# Dual_7seg_Rev0.net
KiCad netlist of a schematic drawn in EAGLE
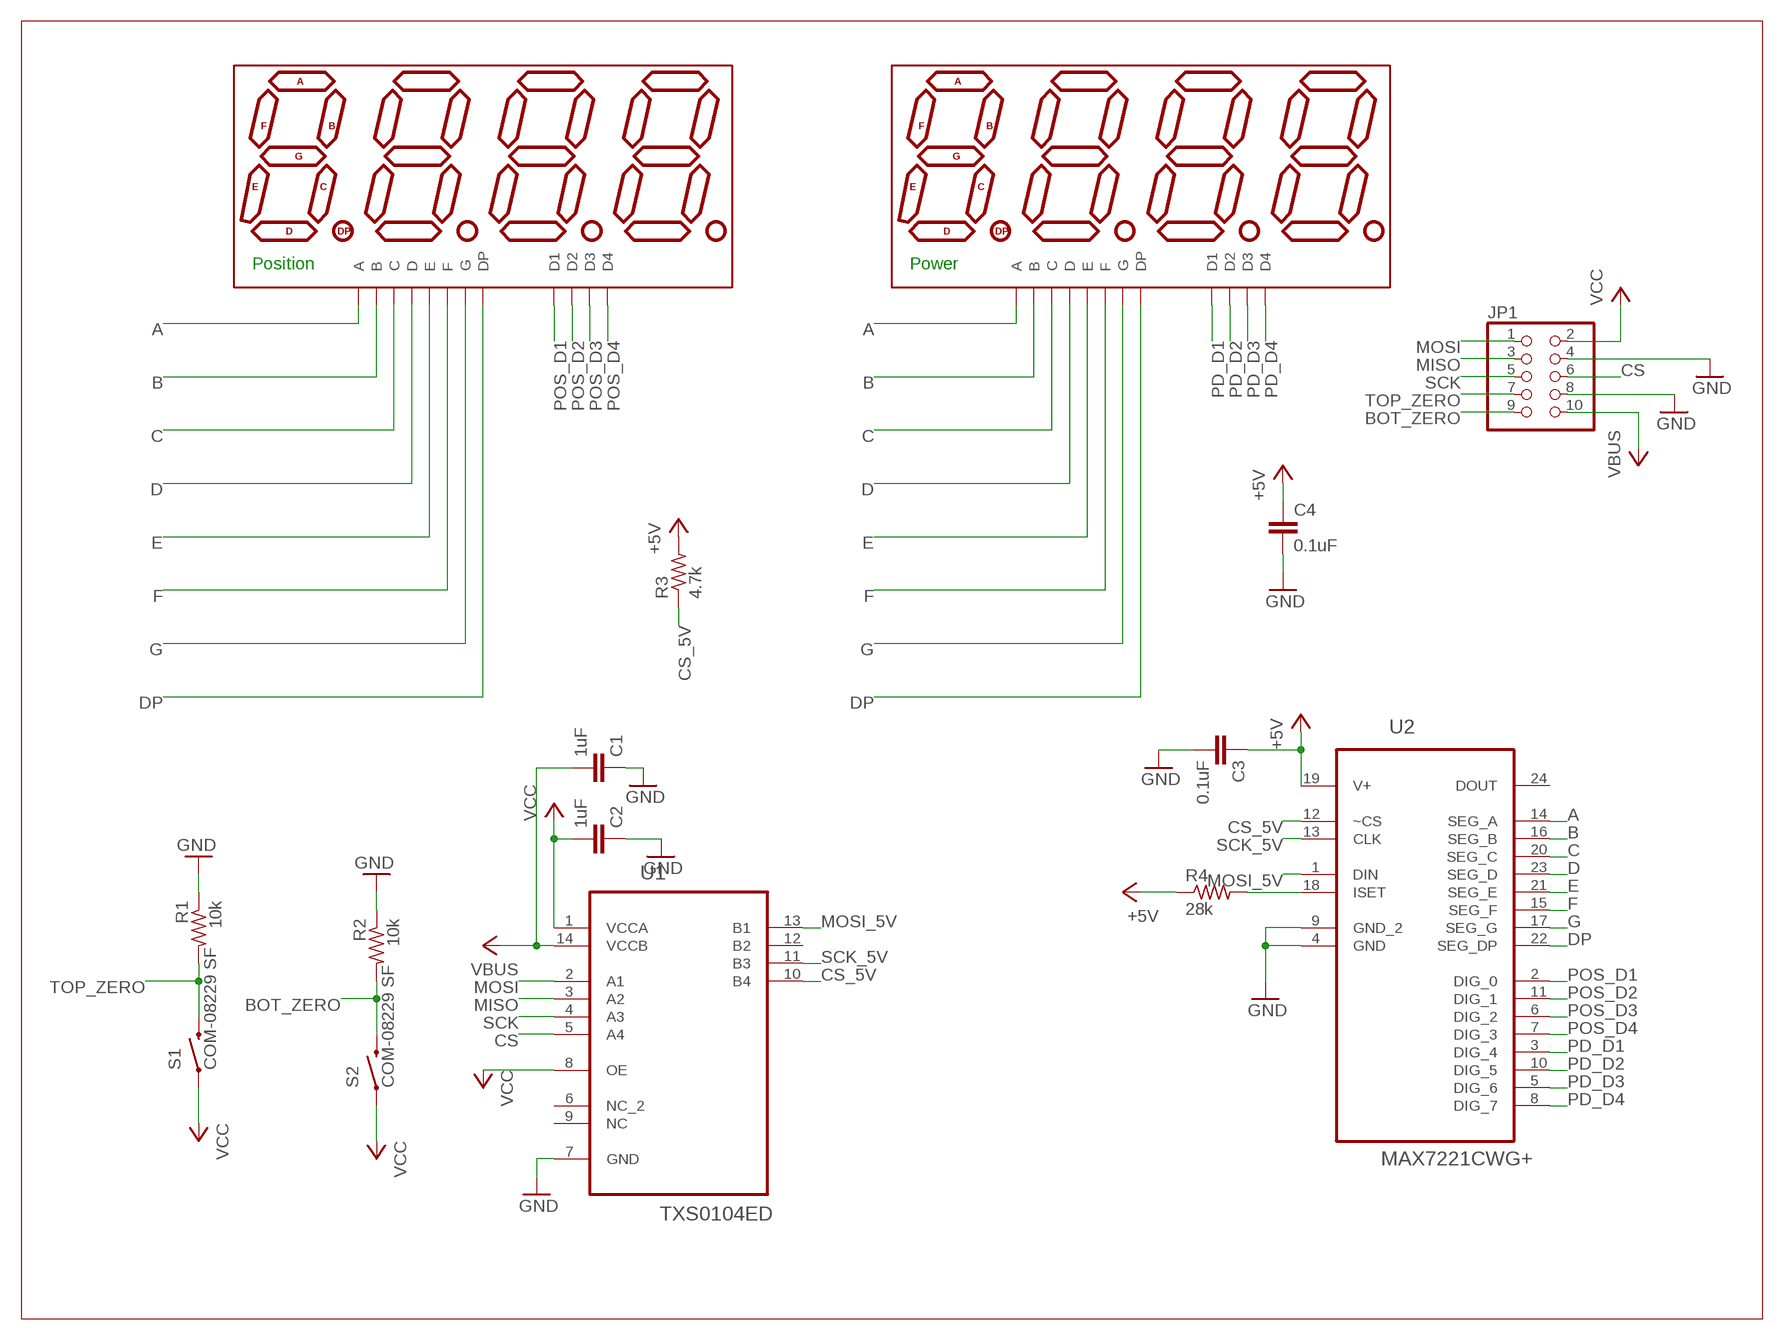
[diagram p0: schematic, sheet 1]

(export (version "E")
  (design (tool "Eeschema 10.0.6"))
  (components
    (comp (ref "C1")
      (value "1uF")
      (footprint "eagle-import:C0402")
      (libsource (lib "eagle-import") (part "C-EUC0402"))
    )
    (comp (ref "C2")
      (value "1uF")
      (footprint "eagle-import:C0402")
      (libsource (lib "eagle-import") (part "C-EUC0402"))
    )
    (comp (ref "C3")
      (value "0.1uF")
      (footprint "eagle-import:C0402")
      (libsource (lib "eagle-import") (part "C-EUC0402"))
    )
    (comp (ref "C4")
      (value "0.1uF")
      (footprint "eagle-import:C0402")
      (libsource (lib "eagle-import") (part "C-EUC0402"))
    )
    (comp (ref "DISP1")
      (value "ATA8041AW")
      (footprint "eagle-import:7-SEGMENT-4DIGIT-20MM")
      (libsource (lib "eagle-import") (part "7-SEGMENT-4DIGIT-20MM-WHITE"))
    )
    (comp (ref "DISP2")
      (value "ATA8041AW")
      (footprint "eagle-import:7-SEGMENT-4DIGIT-20MM")
      (libsource (lib "eagle-import") (part "7-SEGMENT-4DIGIT-20MM-WHITE"))
    )
    (comp (ref "JP1")
      (value "PINHD-2X5")
      (footprint "eagle-import:2X05")
      (libsource (lib "eagle-import") (part "PINHD-2X5"))
    )
    (comp (ref "R1")
      (value "10k")
      (footprint "eagle-import:R0402")
      (libsource (lib "eagle-import") (part "R-US_R0402"))
    )
    (comp (ref "R2")
      (value "10k")
      (footprint "eagle-import:R0402")
      (libsource (lib "eagle-import") (part "R-US_R0402"))
    )
    (comp (ref "R3")
      (value "4.7k")
      (footprint "eagle-import:R0402")
      (libsource (lib "eagle-import") (part "R-US_R0402"))
    )
    (comp (ref "R4")
      (value "28k")
      (footprint "eagle-import:R0402")
      (libsource (lib "eagle-import") (part "R-US_R0402"))
    )
    (comp (ref "S1")
      (value "COM-08229 SF")
      (footprint "eagle-import:TACTILE-SWITCH-1101NE")
      (libsource (lib "eagle-import") (part "SWITCH-MOMENTARY-2SMD-1101NE"))
    )
    (comp (ref "S2")
      (value "COM-08229 SF")
      (footprint "eagle-import:TACTILE-SWITCH-1101NE")
      (libsource (lib "eagle-import") (part "SWITCH-MOMENTARY-2SMD-1101NE"))
    )
    (comp (ref "U1")
      (value "TXS0104ED")
      (footprint "eagle-import:SOIC127P600X175-14N")
      (libsource (lib "eagle-import") (part "TXS0104ED"))
    )
    (comp (ref "U2")
      (value "MAX7221CWG+")
      (footprint "eagle-import:SOIC127P1032X265-24N")
      (libsource (lib "eagle-import") (part "MAX7221CWG+"))
    )
  )
  (nets
    (net (code "1") (name "+5V") (class "Default")
      (node (ref "C1") (pin "2") (pinfunction "2_2") (pintype "passive"))
      (node (ref "C3") (pin "1") (pinfunction "1_1") (pintype "passive"))
      (node (ref "C4") (pin "1") (pinfunction "1_1") (pintype "passive"))
      (node (ref "JP1") (pin "10") (pinfunction "10_10") (pintype "passive"))
      (node (ref "R3") (pin "2") (pinfunction "2_2") (pintype "passive"))
      (node (ref "R4") (pin "1") (pinfunction "1_1") (pintype "passive"))
      (node (ref "U1") (pin "14") (pinfunction "VCCB_14") (pintype "power_in"))
      (node (ref "U2") (pin "19") (pinfunction "V+_19") (pintype "power_in"))
    )
    (net (code "2") (name "/A") (class "Default")
      (node (ref "DISP1") (pin "11") (pinfunction "A_11") (pintype "bidirectional"))
      (node (ref "DISP2") (pin "11") (pinfunction "A_11") (pintype "bidirectional"))
      (node (ref "U2") (pin "14") (pinfunction "SEG_A_14") (pintype "output"))
    )
    (net (code "3") (name "/B") (class "Default")
      (node (ref "DISP1") (pin "7") (pinfunction "B_7") (pintype "bidirectional"))
      (node (ref "DISP2") (pin "7") (pinfunction "B_7") (pintype "bidirectional"))
      (node (ref "U2") (pin "16") (pinfunction "SEG_B_16") (pintype "output"))
    )
    (net (code "4") (name "/BOT_ZERO") (class "Default")
      (node (ref "JP1") (pin "9") (pinfunction "9_9") (pintype "passive"))
      (node (ref "R2") (pin "2") (pinfunction "2_2") (pintype "passive"))
      (node (ref "S2") (pin "2") (pinfunction "2_2") (pintype "passive"))
    )
    (net (code "5") (name "/C") (class "Default")
      (node (ref "DISP1") (pin "4") (pinfunction "C_4") (pintype "bidirectional"))
      (node (ref "DISP2") (pin "4") (pinfunction "C_4") (pintype "bidirectional"))
      (node (ref "U2") (pin "20") (pinfunction "SEG_C_20") (pintype "output"))
    )
    (net (code "6") (name "/CS") (class "Default")
      (node (ref "JP1") (pin "6") (pinfunction "6_6") (pintype "passive"))
      (node (ref "U1") (pin "5") (pinfunction "A4_5") (pintype "input"))
    )
    (net (code "7") (name "/CS_5V") (class "Default")
      (node (ref "R3") (pin "1") (pinfunction "1_1") (pintype "passive"))
      (node (ref "U1") (pin "10") (pinfunction "B4_10") (pintype "output"))
      (node (ref "U2") (pin "12") (pinfunction "~{CS}_12") (pintype "input"))
    )
    (net (code "8") (name "/D") (class "Default")
      (node (ref "DISP1") (pin "2") (pinfunction "D_2") (pintype "bidirectional"))
      (node (ref "DISP2") (pin "2") (pinfunction "D_2") (pintype "bidirectional"))
      (node (ref "U2") (pin "23") (pinfunction "SEG_D_23") (pintype "output"))
    )
    (net (code "9") (name "/DP") (class "Default")
      (node (ref "DISP1") (pin "3") (pinfunction "DP_3") (pintype "bidirectional"))
      (node (ref "DISP2") (pin "3") (pinfunction "DP_3") (pintype "bidirectional"))
      (node (ref "U2") (pin "22") (pinfunction "SEG_DP_22") (pintype "output"))
    )
    (net (code "10") (name "/E") (class "Default")
      (node (ref "DISP1") (pin "1") (pinfunction "E_1") (pintype "bidirectional"))
      (node (ref "DISP2") (pin "1") (pinfunction "E_1") (pintype "bidirectional"))
      (node (ref "U2") (pin "21") (pinfunction "SEG_E_21") (pintype "output"))
    )
    (net (code "11") (name "/F") (class "Default")
      (node (ref "DISP1") (pin "10") (pinfunction "F_10") (pintype "bidirectional"))
      (node (ref "DISP2") (pin "10") (pinfunction "F_10") (pintype "bidirectional"))
      (node (ref "U2") (pin "15") (pinfunction "SEG_F_15") (pintype "output"))
    )
    (net (code "12") (name "/G") (class "Default")
      (node (ref "DISP1") (pin "5") (pinfunction "G_5") (pintype "bidirectional"))
      (node (ref "DISP2") (pin "5") (pinfunction "G_5") (pintype "bidirectional"))
      (node (ref "U2") (pin "17") (pinfunction "SEG_G_17") (pintype "output"))
    )
    (net (code "13") (name "/MISO") (class "Default")
      (node (ref "JP1") (pin "3") (pinfunction "3_3") (pintype "passive"))
      (node (ref "U1") (pin "3") (pinfunction "A2_3") (pintype "input"))
    )
    (net (code "14") (name "/MOSI") (class "Default")
      (node (ref "JP1") (pin "1") (pinfunction "1_1") (pintype "passive"))
      (node (ref "U1") (pin "2") (pinfunction "A1_2") (pintype "input"))
    )
    (net (code "15") (name "/MOSI_5V") (class "Default")
      (node (ref "U1") (pin "13") (pinfunction "B1_13") (pintype "output"))
      (node (ref "U2") (pin "1") (pinfunction "DIN_1") (pintype "input"))
    )
    (net (code "16") (name "/PD_D1") (class "Default")
      (node (ref "DISP2") (pin "12") (pinfunction "D1_12") (pintype "bidirectional"))
      (node (ref "U2") (pin "3") (pinfunction "DIG_4_3") (pintype "output"))
    )
    (net (code "17") (name "/PD_D2") (class "Default")
      (node (ref "DISP2") (pin "9") (pinfunction "D2_9") (pintype "bidirectional"))
      (node (ref "U2") (pin "10") (pinfunction "DIG_5_10") (pintype "output"))
    )
    (net (code "18") (name "/PD_D3") (class "Default")
      (node (ref "DISP2") (pin "8") (pinfunction "D3_8") (pintype "bidirectional"))
      (node (ref "U2") (pin "5") (pinfunction "DIG_6_5") (pintype "output"))
    )
    (net (code "19") (name "/PD_D4") (class "Default")
      (node (ref "DISP2") (pin "6") (pinfunction "D4_6") (pintype "bidirectional"))
      (node (ref "U2") (pin "8") (pinfunction "DIG_7_8") (pintype "output"))
    )
    (net (code "20") (name "/POS_D1") (class "Default")
      (node (ref "DISP1") (pin "12") (pinfunction "D1_12") (pintype "bidirectional"))
      (node (ref "U2") (pin "2") (pinfunction "DIG_0_2") (pintype "output"))
    )
    (net (code "21") (name "/POS_D2") (class "Default")
      (node (ref "DISP1") (pin "9") (pinfunction "D2_9") (pintype "bidirectional"))
      (node (ref "U2") (pin "11") (pinfunction "DIG_1_11") (pintype "output"))
    )
    (net (code "22") (name "/POS_D3") (class "Default")
      (node (ref "DISP1") (pin "8") (pinfunction "D3_8") (pintype "bidirectional"))
      (node (ref "U2") (pin "6") (pinfunction "DIG_2_6") (pintype "output"))
    )
    (net (code "23") (name "/POS_D4") (class "Default")
      (node (ref "DISP1") (pin "6") (pinfunction "D4_6") (pintype "bidirectional"))
      (node (ref "U2") (pin "7") (pinfunction "DIG_3_7") (pintype "output"))
    )
    (net (code "24") (name "/SCK") (class "Default")
      (node (ref "JP1") (pin "5") (pinfunction "5_5") (pintype "passive"))
      (node (ref "U1") (pin "4") (pinfunction "A3_4") (pintype "input"))
    )
    (net (code "25") (name "/SCK_5V") (class "Default")
      (node (ref "U1") (pin "11") (pinfunction "B3_11") (pintype "output"))
      (node (ref "U2") (pin "13") (pinfunction "CLK_13") (pintype "input"))
    )
    (net (code "26") (name "/TOP_ZERO") (class "Default")
      (node (ref "JP1") (pin "7") (pinfunction "7_7") (pintype "passive"))
      (node (ref "R1") (pin "2") (pinfunction "2_2") (pintype "passive"))
      (node (ref "S1") (pin "2") (pinfunction "2_2") (pintype "passive"))
    )
    (net (code "27") (name "GND") (class "Default")
      (node (ref "C1") (pin "1") (pinfunction "1_1") (pintype "passive"))
      (node (ref "C2") (pin "1") (pinfunction "1_1") (pintype "passive"))
      (node (ref "C3") (pin "2") (pinfunction "2_2") (pintype "passive"))
      (node (ref "C4") (pin "2") (pinfunction "2_2") (pintype "passive"))
      (node (ref "JP1") (pin "4") (pinfunction "4_4") (pintype "passive"))
      (node (ref "JP1") (pin "8") (pinfunction "8_8") (pintype "passive"))
      (node (ref "R1") (pin "1") (pinfunction "1_1") (pintype "passive"))
      (node (ref "R2") (pin "1") (pinfunction "1_1") (pintype "passive"))
      (node (ref "U1") (pin "7") (pinfunction "GND_7") (pintype "passive"))
      (node (ref "U2") (pin "4") (pinfunction "GND_4") (pintype "passive"))
      (node (ref "U2") (pin "9") (pinfunction "GND_2_9") (pintype "passive"))
    )
    (net (code "28") (name "Net-(U2-ISET)") (class "Default")
      (node (ref "R4") (pin "2") (pinfunction "2_2") (pintype "passive"))
      (node (ref "U2") (pin "18") (pinfunction "ISET_18") (pintype "input"))
    )
    (net (code "29") (name "VCC") (class "Default")
      (node (ref "C2") (pin "2") (pinfunction "2_2") (pintype "passive"))
      (node (ref "JP1") (pin "2") (pinfunction "2_2") (pintype "passive"))
      (node (ref "S1") (pin "1") (pinfunction "1_1") (pintype "passive"))
      (node (ref "S2") (pin "1") (pinfunction "1_1") (pintype "passive"))
      (node (ref "U1") (pin "1") (pinfunction "VCCA_1") (pintype "power_in"))
      (node (ref "U1") (pin "8") (pinfunction "OE_8") (pintype "input"))
    )
    (net (code "30") (name "unconnected-(U1-B2-Pad12)") (class "Default")
      (node (ref "U1") (pin "12") (pinfunction "B2_12") (pintype "output"))
    )
    (net (code "31") (name "unconnected-(U1-NC-Pad9)") (class "Default")
      (node (ref "U1") (pin "9") (pinfunction "NC_9") (pintype "no_connect"))
    )
    (net (code "32") (name "unconnected-(U1-NC_2-Pad6)") (class "Default")
      (node (ref "U1") (pin "6") (pinfunction "NC_2_6") (pintype "no_connect"))
    )
    (net (code "33") (name "unconnected-(U2-DOUT-Pad24)") (class "Default")
      (node (ref "U2") (pin "24") (pinfunction "DOUT_24") (pintype "output"))
    )
  )
)
